# linefollower.net
KiCad netlist of a schematic drawn in EAGLE
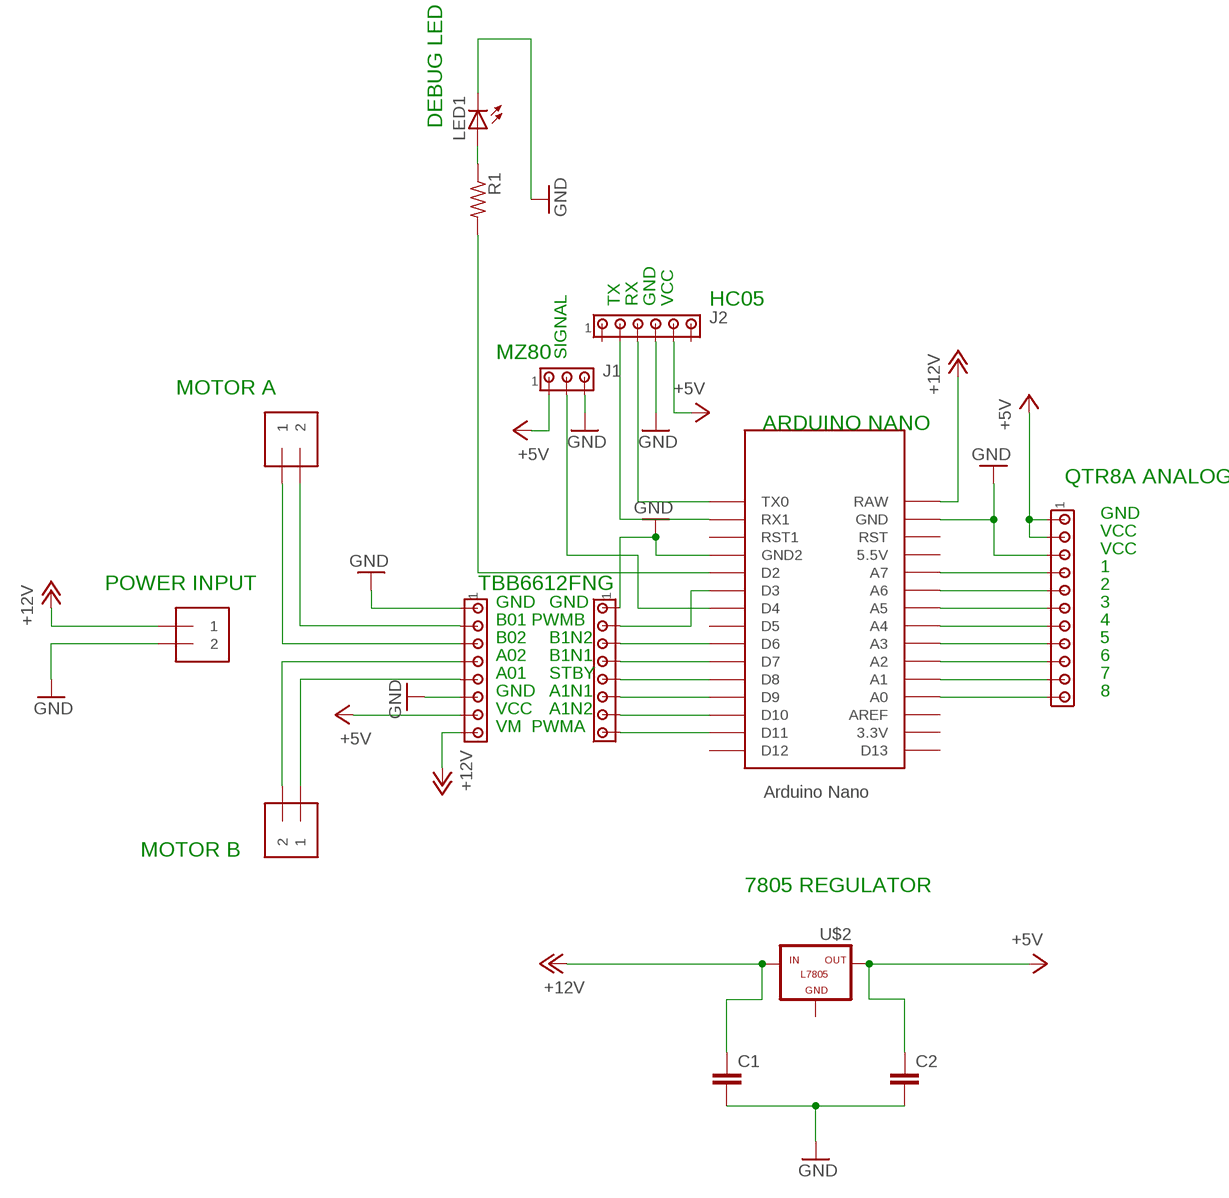
[diagram p0: schematic, sheet 1]

(export (version "E")
  (design (tool "Eeschema 10.0.6"))
  (components
    (comp (ref "C1")
      (value "C-EUC0805")
      (footprint "eagle-import:C0805")
      (libsource (lib "eagle-import") (part "C-EUC0805"))
    )
    (comp (ref "C2")
      (value "C-EUC0805")
      (footprint "eagle-import:C0805")
      (libsource (lib "eagle-import") (part "C-EUC0805"))
    )
    (comp (ref "J1")
      (value "MTA03-100")
      (footprint "eagle-import:10X03MTA")
      (libsource (lib "eagle-import") (part "MTA03-100"))
    )
    (comp (ref "J2")
      (value "MTA06-100")
      (footprint "eagle-import:10X06MTA")
      (libsource (lib "eagle-import") (part "MTA06-100"))
    )
    (comp (ref "LED1")
      (value "LED-0805")
      (footprint "eagle-import:LED-805")
      (libsource (lib "eagle-import") (part "LED-0805"))
    )
    (comp (ref "MOTORA")
      (value "1X2-3.5MM")
      (footprint "eagle-import:3.5MMTERM")
      (libsource (lib "eagle-import") (part "1X2-3.5MM"))
    )
    (comp (ref "MOTORB")
      (value "1X2-3.5MM")
      (footprint "eagle-import:3.5MMTERM")
      (libsource (lib "eagle-import") (part "1X2-3.5MM"))
    )
    (comp (ref "POWER")
      (value "1X2-3.5MM")
      (footprint "eagle-import:3.5MMTERM")
      (libsource (lib "eagle-import") (part "1X2-3.5MM"))
    )
    (comp (ref "QTR8A")
      (value "MTA11-156")
      (footprint "eagle-import:1X11MTA")
      (libsource (lib "eagle-import") (part "MTA11-156"))
    )
    (comp (ref "R1")
      (value "R-US_R0805")
      (footprint "eagle-import:R0805")
      (libsource (lib "eagle-import") (part "R-US_R0805"))
    )
    (comp (ref "TBB6612FNGLEFT")
      (value "MTA08-100")
      (footprint "eagle-import:10X08MTA")
      (libsource (lib "eagle-import") (part "MTA08-100"))
    )
    (comp (ref "TBB6612FNGRıGHT")
      (value "MTA08-100")
      (footprint "eagle-import:10X08MTA")
      (libsource (lib "eagle-import") (part "MTA08-100"))
    )
    (comp (ref "U$1")
      (value "NANO")
      (footprint "eagle-import:NANO")
      (libsource (lib "eagle-import") (part "NANO"))
    )
    (comp (ref "U$2")
      (value "-L7805")
      (footprint "eagle-import:L7805")
      (libsource (lib "eagle-import") (part "-L7805"))
    )
  )
  (nets
    (net (code "1") (name "+5V") (class "Default")
      (node (ref "C2") (pin "1") (pinfunction "1_1") (pintype "passive"))
      (node (ref "J1") (pin "1") (pinfunction "1_1") (pintype "passive"))
      (node (ref "J2") (pin "5") (pinfunction "5_5") (pintype "passive"))
      (node (ref "QTR8A") (pin "1") (pinfunction "1_1") (pintype "passive"))
      (node (ref "QTR8A") (pin "2") (pinfunction "2_2") (pintype "passive"))
      (node (ref "TBB6612FNGLEFT") (pin "7") (pinfunction "7_7") (pintype "passive"))
      (node (ref "U$2") (pin "OUT") (pinfunction "OUT_OUT") (pintype "passive"))
    )
    (net (code "2") (name "+12V") (class "Default")
      (node (ref "C1") (pin "1") (pinfunction "1_1") (pintype "passive"))
      (node (ref "POWER") (pin "1") (pinfunction "1_1") (pintype "passive"))
      (node (ref "TBB6612FNGLEFT") (pin "8") (pinfunction "8_8") (pintype "passive"))
      (node (ref "U$1") (pin "RAW") (pinfunction "RAW_RAW") (pintype "bidirectional"))
      (node (ref "U$2") (pin "IN") (pinfunction "IN_IN") (pintype "input"))
    )
    (net (code "3") (name "GND") (class "Default")
      (node (ref "C1") (pin "2") (pinfunction "2_2") (pintype "passive"))
      (node (ref "C2") (pin "2") (pinfunction "2_2") (pintype "passive"))
      (node (ref "J1") (pin "3") (pinfunction "3_3") (pintype "passive"))
      (node (ref "J2") (pin "4") (pinfunction "4_4") (pintype "passive"))
      (node (ref "LED1") (pin "C") (pinfunction "C_C") (pintype "passive"))
      (node (ref "POWER") (pin "2") (pinfunction "2_2") (pintype "passive"))
      (node (ref "QTR8A") (pin "3") (pinfunction "3_3") (pintype "passive"))
      (node (ref "TBB6612FNGLEFT") (pin "1") (pinfunction "1_1") (pintype "passive"))
      (node (ref "TBB6612FNGLEFT") (pin "6") (pinfunction "6_6") (pintype "passive"))
      (node (ref "TBB6612FNGRıGHT") (pin "1") (pinfunction "1_1") (pintype "passive"))
      (node (ref "U$1") (pin "GND") (pinfunction "GND_GND") (pintype "bidirectional"))
      (node (ref "U$1") (pin "GND1") (pinfunction "GND2_GND1") (pintype "bidirectional"))
    )
    (net (code "4") (name "Net-(J1-Pad2)") (class "Default")
      (node (ref "J1") (pin "2") (pinfunction "2_2") (pintype "passive"))
      (node (ref "U$1") (pin "D4") (pinfunction "D4_D4") (pintype "bidirectional"))
    )
    (net (code "5") (name "Net-(J2-Pad2)") (class "Default")
      (node (ref "J2") (pin "2") (pinfunction "2_2") (pintype "passive"))
      (node (ref "U$1") (pin "RX1") (pinfunction "RX1_RX1") (pintype "bidirectional"))
    )
    (net (code "6") (name "Net-(J2-Pad3)") (class "Default")
      (node (ref "J2") (pin "3") (pinfunction "3_3") (pintype "passive"))
      (node (ref "U$1") (pin "TX0") (pinfunction "TX0_TX0") (pintype "bidirectional"))
    )
    (net (code "7") (name "Net-(LED1-PadA)") (class "Default")
      (node (ref "LED1") (pin "A") (pinfunction "A_A") (pintype "passive"))
      (node (ref "R1") (pin "1") (pinfunction "1_1") (pintype "passive"))
    )
    (net (code "8") (name "Net-(MOTORA-Pad1)") (class "Default")
      (node (ref "MOTORA") (pin "1") (pinfunction "1_1") (pintype "passive"))
      (node (ref "TBB6612FNGLEFT") (pin "3") (pinfunction "3_3") (pintype "passive"))
    )
    (net (code "9") (name "Net-(MOTORA-Pad2)") (class "Default")
      (node (ref "MOTORA") (pin "2") (pinfunction "2_2") (pintype "passive"))
      (node (ref "TBB6612FNGLEFT") (pin "2") (pinfunction "2_2") (pintype "passive"))
    )
    (net (code "10") (name "Net-(MOTORB-Pad1)") (class "Default")
      (node (ref "MOTORB") (pin "1") (pinfunction "1_1") (pintype "passive"))
      (node (ref "TBB6612FNGLEFT") (pin "5") (pinfunction "5_5") (pintype "passive"))
    )
    (net (code "11") (name "Net-(MOTORB-Pad2)") (class "Default")
      (node (ref "MOTORB") (pin "2") (pinfunction "2_2") (pintype "passive"))
      (node (ref "TBB6612FNGLEFT") (pin "4") (pinfunction "4_4") (pintype "passive"))
    )
    (net (code "12") (name "Net-(QTR8A-Pad4)") (class "Default")
      (node (ref "QTR8A") (pin "4") (pinfunction "4_4") (pintype "passive"))
      (node (ref "U$1") (pin "A7") (pinfunction "A7_A7") (pintype "bidirectional"))
    )
    (net (code "13") (name "Net-(QTR8A-Pad5)") (class "Default")
      (node (ref "QTR8A") (pin "5") (pinfunction "5_5") (pintype "passive"))
      (node (ref "U$1") (pin "A6") (pinfunction "A6_A6") (pintype "bidirectional"))
    )
    (net (code "14") (name "Net-(QTR8A-Pad6)") (class "Default")
      (node (ref "QTR8A") (pin "6") (pinfunction "6_6") (pintype "passive"))
      (node (ref "U$1") (pin "A5") (pinfunction "A5_A5") (pintype "bidirectional"))
    )
    (net (code "15") (name "Net-(QTR8A-Pad7)") (class "Default")
      (node (ref "QTR8A") (pin "7") (pinfunction "7_7") (pintype "passive"))
      (node (ref "U$1") (pin "A4") (pinfunction "A4_A4") (pintype "bidirectional"))
    )
    (net (code "16") (name "Net-(QTR8A-Pad8)") (class "Default")
      (node (ref "QTR8A") (pin "8") (pinfunction "8_8") (pintype "passive"))
      (node (ref "U$1") (pin "A3") (pinfunction "A3_A3") (pintype "bidirectional"))
    )
    (net (code "17") (name "Net-(QTR8A-Pad9)") (class "Default")
      (node (ref "QTR8A") (pin "9") (pinfunction "9_9") (pintype "passive"))
      (node (ref "U$1") (pin "A2") (pinfunction "A2_A2") (pintype "bidirectional"))
    )
    (net (code "18") (name "Net-(QTR8A-Pad10)") (class "Default")
      (node (ref "QTR8A") (pin "10") (pinfunction "10_10") (pintype "passive"))
      (node (ref "U$1") (pin "A1") (pinfunction "A1_A1") (pintype "bidirectional"))
    )
    (net (code "19") (name "Net-(QTR8A-Pad11)") (class "Default")
      (node (ref "QTR8A") (pin "11") (pinfunction "11_11") (pintype "passive"))
      (node (ref "U$1") (pin "A0") (pinfunction "A0_A0") (pintype "bidirectional"))
    )
    (net (code "20") (name "Net-(R1-Pad2)") (class "Default")
      (node (ref "R1") (pin "2") (pinfunction "2_2") (pintype "passive"))
      (node (ref "U$1") (pin "D2") (pinfunction "D2_D2") (pintype "bidirectional"))
    )
    (net (code "21") (name "Net-(TBB6612FNGRıGHT-Pad2)") (class "Default")
      (node (ref "TBB6612FNGRıGHT") (pin "2") (pinfunction "2_2") (pintype "passive"))
      (node (ref "U$1") (pin "D3") (pinfunction "D3_D3") (pintype "bidirectional"))
    )
    (net (code "22") (name "Net-(TBB6612FNGRıGHT-Pad3)") (class "Default")
      (node (ref "TBB6612FNGRıGHT") (pin "3") (pinfunction "3_3") (pintype "passive"))
      (node (ref "U$1") (pin "D6") (pinfunction "D6_D6") (pintype "bidirectional"))
    )
    (net (code "23") (name "Net-(TBB6612FNGRıGHT-Pad4)") (class "Default")
      (node (ref "TBB6612FNGRıGHT") (pin "4") (pinfunction "4_4") (pintype "passive"))
      (node (ref "U$1") (pin "D7") (pinfunction "D7_D7") (pintype "bidirectional"))
    )
    (net (code "24") (name "Net-(TBB6612FNGRıGHT-Pad5)") (class "Default")
      (node (ref "TBB6612FNGRıGHT") (pin "5") (pinfunction "5_5") (pintype "passive"))
      (node (ref "U$1") (pin "D8") (pinfunction "D8_D8") (pintype "bidirectional"))
    )
    (net (code "25") (name "Net-(TBB6612FNGRıGHT-Pad6)") (class "Default")
      (node (ref "TBB6612FNGRıGHT") (pin "6") (pinfunction "6_6") (pintype "passive"))
      (node (ref "U$1") (pin "D9") (pinfunction "D9_D9") (pintype "bidirectional"))
    )
    (net (code "26") (name "Net-(TBB6612FNGRıGHT-Pad7)") (class "Default")
      (node (ref "TBB6612FNGRıGHT") (pin "7") (pinfunction "7_7") (pintype "passive"))
      (node (ref "U$1") (pin "D10") (pinfunction "D10_D10") (pintype "bidirectional"))
    )
    (net (code "27") (name "Net-(TBB6612FNGRıGHT-Pad8)") (class "Default")
      (node (ref "TBB6612FNGRıGHT") (pin "8") (pinfunction "8_8") (pintype "passive"))
      (node (ref "U$1") (pin "D11") (pinfunction "D11_D11") (pintype "bidirectional"))
    )
    (net (code "28") (name "unconnected-(J2-Pad1)") (class "Default")
      (node (ref "J2") (pin "1") (pinfunction "1_1") (pintype "passive"))
    )
    (net (code "29") (name "unconnected-(J2-Pad6)") (class "Default")
      (node (ref "J2") (pin "6") (pinfunction "6_6") (pintype "passive"))
    )
    (net (code "30") (name "unconnected-(U$1-5.5V-Pad5V)") (class "Default")
      (node (ref "U$1") (pin "5V") (pinfunction "5.5V_5V") (pintype "bidirectional"))
    )
    (net (code "31") (name "unconnected-(U$1-Pad3.3V)") (class "Default")
      (node (ref "U$1") (pin "3.3V") (pinfunction "3.3V_3.3V") (pintype "bidirectional"))
    )
    (net (code "32") (name "unconnected-(U$1-PadAREF)") (class "Default")
      (node (ref "U$1") (pin "AREF") (pinfunction "AREF_AREF") (pintype "bidirectional"))
    )
    (net (code "33") (name "unconnected-(U$1-PadD5)") (class "Default")
      (node (ref "U$1") (pin "D5") (pinfunction "D5_D5") (pintype "bidirectional"))
    )
    (net (code "34") (name "unconnected-(U$1-PadD12)") (class "Default")
      (node (ref "U$1") (pin "D12") (pinfunction "D12_D12") (pintype "bidirectional"))
    )
    (net (code "35") (name "unconnected-(U$1-PadD13)") (class "Default")
      (node (ref "U$1") (pin "D13") (pinfunction "D13_D13") (pintype "bidirectional"))
    )
    (net (code "36") (name "unconnected-(U$1-PadICSP1)") (class "Default")
      (node (ref "U$1") (pin "ICSP1") (pinfunction "ICSP1_ICSP1") (pintype "bidirectional"))
    )
    (net (code "37") (name "unconnected-(U$1-PadICSP2)") (class "Default")
      (node (ref "U$1") (pin "ICSP2") (pinfunction "ICSP2_ICSP2") (pintype "bidirectional"))
    )
    (net (code "38") (name "unconnected-(U$1-PadICSP3)") (class "Default")
      (node (ref "U$1") (pin "ICSP3") (pinfunction "ICSP3_ICSP3") (pintype "bidirectional"))
    )
    (net (code "39") (name "unconnected-(U$1-PadICSP4)") (class "Default")
      (node (ref "U$1") (pin "ICSP4") (pinfunction "ICSP4_ICSP4") (pintype "bidirectional"))
    )
    (net (code "40") (name "unconnected-(U$1-PadICSP5)") (class "Default")
      (node (ref "U$1") (pin "ICSP5") (pinfunction "ICSP5_ICSP5") (pintype "bidirectional"))
    )
    (net (code "41") (name "unconnected-(U$1-PadICSP6)") (class "Default")
      (node (ref "U$1") (pin "ICSP6") (pinfunction "ICSP6_ICSP6") (pintype "bidirectional"))
    )
    (net (code "42") (name "unconnected-(U$1-PadRST)") (class "Default")
      (node (ref "U$1") (pin "RST") (pinfunction "RST_RST") (pintype "bidirectional"))
    )
    (net (code "43") (name "unconnected-(U$1-PadRST1)") (class "Default")
      (node (ref "U$1") (pin "RST1") (pinfunction "RST1_RST1") (pintype "bidirectional"))
    )
    (net (code "44") (name "unconnected-(U$2-PadGND)") (class "Default")
      (node (ref "U$2") (pin "GND") (pinfunction "GND_GND") (pintype "input"))
    )
  )
)
